# version1_3.net
KiCad netlist of a schematic drawn in EAGLE
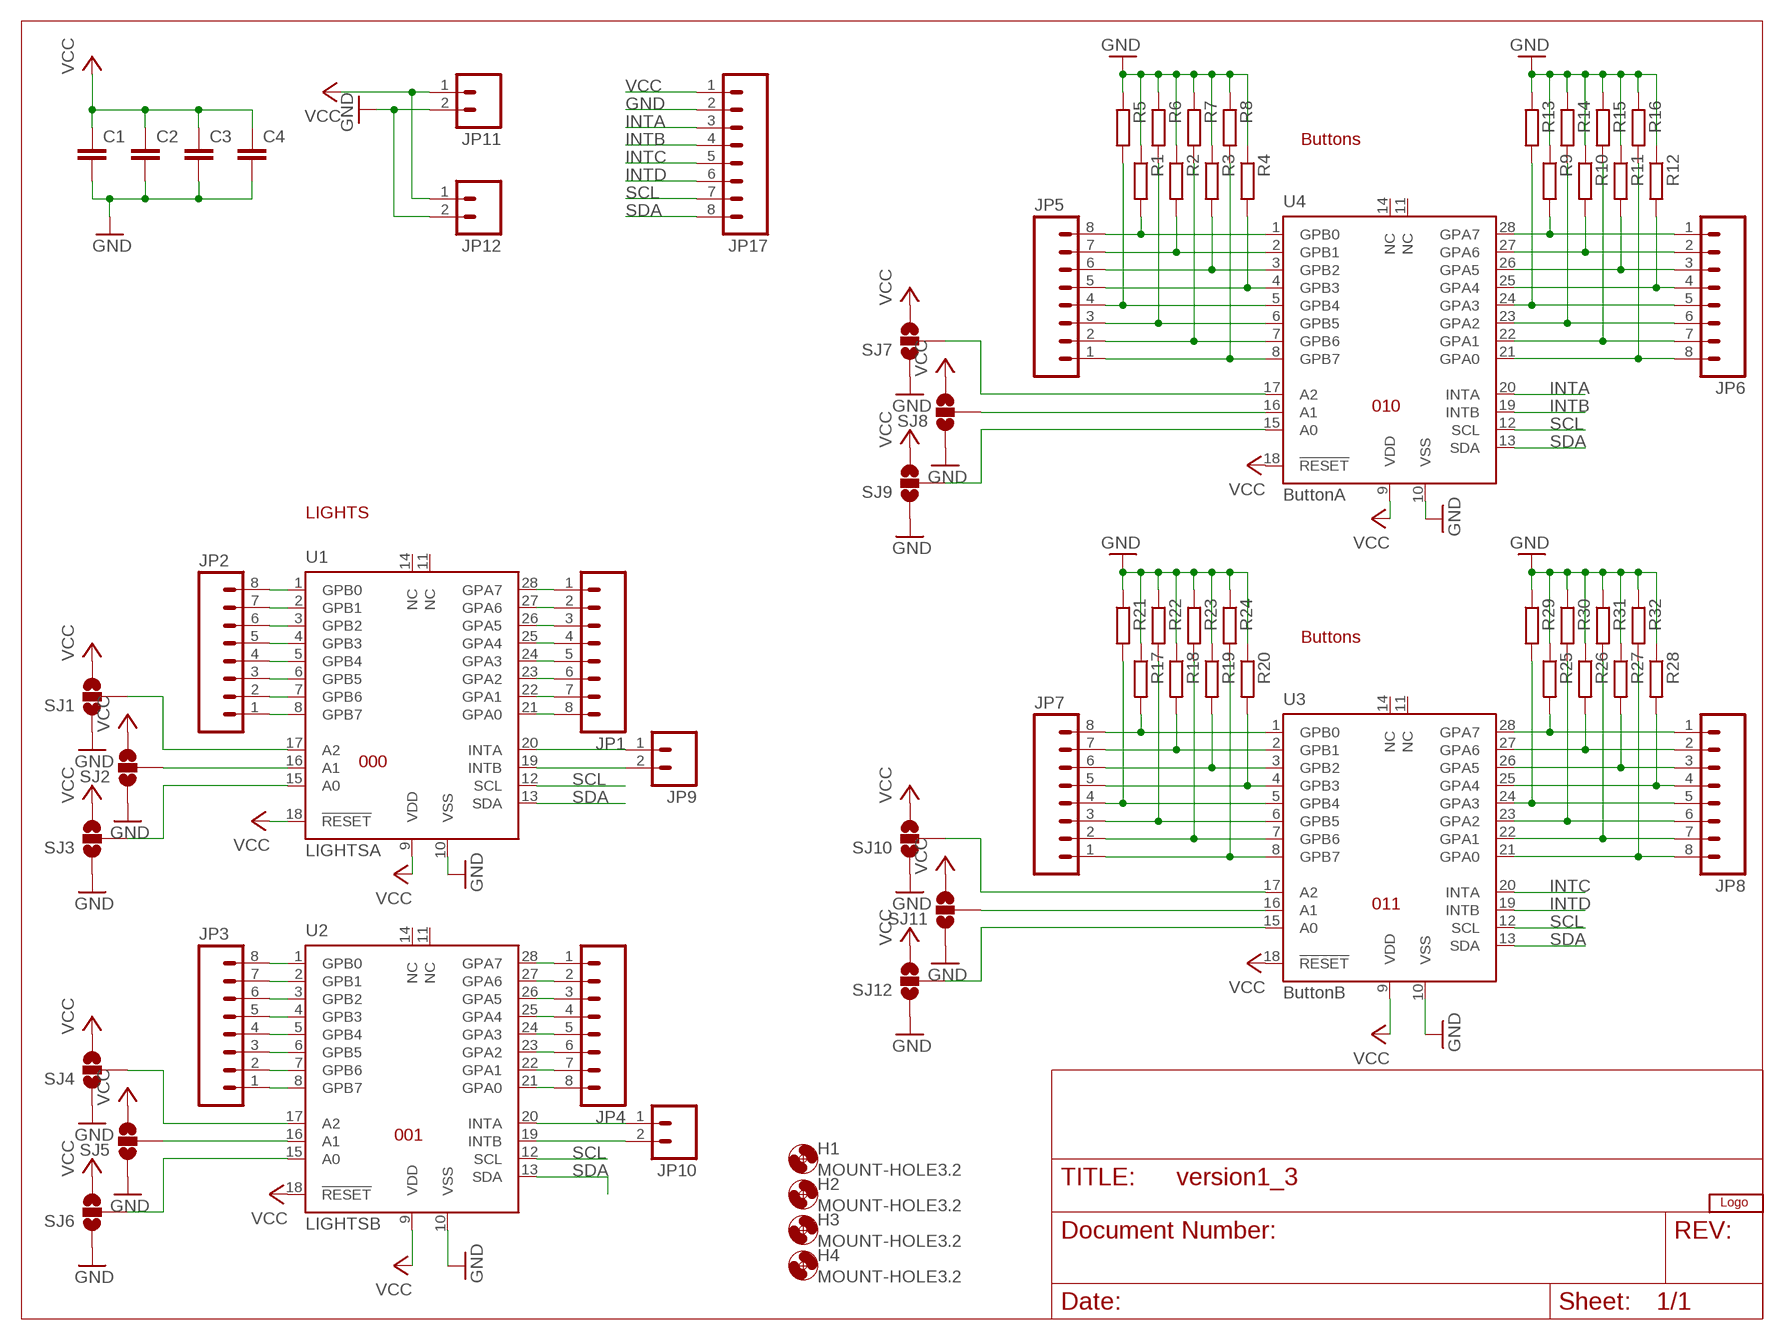
[diagram p0: schematic, sheet 1]

(export (version "E")
  (design (tool "Eeschema 10.0.6"))
  (components
    (comp (ref "C1")
      (value "C-EUC0805")
      (footprint "eagle-import:C0805")
      (libsource (lib "eagle-import") (part "C-EUC0805"))
    )
    (comp (ref "C2")
      (value "C-EUC0805")
      (footprint "eagle-import:C0805")
      (libsource (lib "eagle-import") (part "C-EUC0805"))
    )
    (comp (ref "C3")
      (value "C-EUC0805")
      (footprint "eagle-import:C0805")
      (libsource (lib "eagle-import") (part "C-EUC0805"))
    )
    (comp (ref "C4")
      (value "C-EUC0805")
      (footprint "eagle-import:C0805")
      (libsource (lib "eagle-import") (part "C-EUC0805"))
    )
    (comp (ref "H1")
      (value "MOUNT-HOLE3.2")
      (footprint "eagle-import:3,2")
      (libsource (lib "eagle-import") (part "MOUNT-HOLE3.2"))
    )
    (comp (ref "H2")
      (value "MOUNT-HOLE3.2")
      (footprint "eagle-import:3,2")
      (libsource (lib "eagle-import") (part "MOUNT-HOLE3.2"))
    )
    (comp (ref "H3")
      (value "MOUNT-HOLE3.2")
      (footprint "eagle-import:3,2")
      (libsource (lib "eagle-import") (part "MOUNT-HOLE3.2"))
    )
    (comp (ref "H4")
      (value "MOUNT-HOLE3.2")
      (footprint "eagle-import:3,2")
      (libsource (lib "eagle-import") (part "MOUNT-HOLE3.2"))
    )
    (comp (ref "JP1")
      (value "M08LOCK")
      (footprint "eagle-import:1X08_LOCK")
      (libsource (lib "eagle-import") (part "M08LOCK"))
    )
    (comp (ref "JP2")
      (value "M08LOCK")
      (footprint "eagle-import:1X08_LOCK")
      (libsource (lib "eagle-import") (part "M08LOCK"))
    )
    (comp (ref "JP3")
      (value "M08LOCK")
      (footprint "eagle-import:1X08_LOCK")
      (libsource (lib "eagle-import") (part "M08LOCK"))
    )
    (comp (ref "JP4")
      (value "M08LOCK")
      (footprint "eagle-import:1X08_LOCK")
      (libsource (lib "eagle-import") (part "M08LOCK"))
    )
    (comp (ref "JP5")
      (value "M08LOCK")
      (footprint "eagle-import:1X08_LOCK")
      (libsource (lib "eagle-import") (part "M08LOCK"))
    )
    (comp (ref "JP6")
      (value "M08LOCK")
      (footprint "eagle-import:1X08_LOCK")
      (libsource (lib "eagle-import") (part "M08LOCK"))
    )
    (comp (ref "JP7")
      (value "M08LOCK")
      (footprint "eagle-import:1X08_LOCK")
      (libsource (lib "eagle-import") (part "M08LOCK"))
    )
    (comp (ref "JP8")
      (value "M08LOCK")
      (footprint "eagle-import:1X08_LOCK")
      (libsource (lib "eagle-import") (part "M08LOCK"))
    )
    (comp (ref "JP9")
      (value "M021X02_NO_SILK")
      (footprint "eagle-import:1X02_NO_SILK")
      (libsource (lib "eagle-import") (part "M021X02_NO_SILK"))
    )
    (comp (ref "JP10")
      (value "M021X02_NO_SILK")
      (footprint "eagle-import:1X02_NO_SILK")
      (libsource (lib "eagle-import") (part "M021X02_NO_SILK"))
    )
    (comp (ref "JP11")
      (value "M021X02_NO_SILK")
      (footprint "eagle-import:1X02_NO_SILK")
      (libsource (lib "eagle-import") (part "M021X02_NO_SILK"))
    )
    (comp (ref "JP12")
      (value "M021X02_NO_SILK")
      (footprint "eagle-import:1X02_NO_SILK")
      (libsource (lib "eagle-import") (part "M021X02_NO_SILK"))
    )
    (comp (ref "JP17")
      (value "M08LOCK")
      (footprint "eagle-import:1X08_LOCK")
      (libsource (lib "eagle-import") (part "M08LOCK"))
    )
    (comp (ref "R1")
      (value "R-EU_R0805")
      (footprint "eagle-import:R0805")
      (libsource (lib "eagle-import") (part "R-EU_R0805"))
    )
    (comp (ref "R2")
      (value "R-EU_R0805")
      (footprint "eagle-import:R0805")
      (libsource (lib "eagle-import") (part "R-EU_R0805"))
    )
    (comp (ref "R3")
      (value "R-EU_R0805")
      (footprint "eagle-import:R0805")
      (libsource (lib "eagle-import") (part "R-EU_R0805"))
    )
    (comp (ref "R4")
      (value "R-EU_R0805")
      (footprint "eagle-import:R0805")
      (libsource (lib "eagle-import") (part "R-EU_R0805"))
    )
    (comp (ref "R5")
      (value "R-EU_R0805")
      (footprint "eagle-import:R0805")
      (libsource (lib "eagle-import") (part "R-EU_R0805"))
    )
    (comp (ref "R6")
      (value "R-EU_R0805")
      (footprint "eagle-import:R0805")
      (libsource (lib "eagle-import") (part "R-EU_R0805"))
    )
    (comp (ref "R7")
      (value "R-EU_R0805")
      (footprint "eagle-import:R0805")
      (libsource (lib "eagle-import") (part "R-EU_R0805"))
    )
    (comp (ref "R8")
      (value "R-EU_R0805")
      (footprint "eagle-import:R0805")
      (libsource (lib "eagle-import") (part "R-EU_R0805"))
    )
    (comp (ref "R9")
      (value "R-EU_R0805")
      (footprint "eagle-import:R0805")
      (libsource (lib "eagle-import") (part "R-EU_R0805"))
    )
    (comp (ref "R10")
      (value "R-EU_R0805")
      (footprint "eagle-import:R0805")
      (libsource (lib "eagle-import") (part "R-EU_R0805"))
    )
    (comp (ref "R11")
      (value "R-EU_R0805")
      (footprint "eagle-import:R0805")
      (libsource (lib "eagle-import") (part "R-EU_R0805"))
    )
    (comp (ref "R12")
      (value "R-EU_R0805")
      (footprint "eagle-import:R0805")
      (libsource (lib "eagle-import") (part "R-EU_R0805"))
    )
    (comp (ref "R13")
      (value "R-EU_R0805")
      (footprint "eagle-import:R0805")
      (libsource (lib "eagle-import") (part "R-EU_R0805"))
    )
    (comp (ref "R14")
      (value "R-EU_R0805")
      (footprint "eagle-import:R0805")
      (libsource (lib "eagle-import") (part "R-EU_R0805"))
    )
    (comp (ref "R15")
      (value "R-EU_R0805")
      (footprint "eagle-import:R0805")
      (libsource (lib "eagle-import") (part "R-EU_R0805"))
    )
    (comp (ref "R16")
      (value "R-EU_R0805")
      (footprint "eagle-import:R0805")
      (libsource (lib "eagle-import") (part "R-EU_R0805"))
    )
    (comp (ref "R17")
      (value "R-EU_R0805")
      (footprint "eagle-import:R0805")
      (libsource (lib "eagle-import") (part "R-EU_R0805"))
    )
    (comp (ref "R18")
      (value "R-EU_R0805")
      (footprint "eagle-import:R0805")
      (libsource (lib "eagle-import") (part "R-EU_R0805"))
    )
    (comp (ref "R19")
      (value "R-EU_R0805")
      (footprint "eagle-import:R0805")
      (libsource (lib "eagle-import") (part "R-EU_R0805"))
    )
    (comp (ref "R20")
      (value "R-EU_R0805")
      (footprint "eagle-import:R0805")
      (libsource (lib "eagle-import") (part "R-EU_R0805"))
    )
    (comp (ref "R21")
      (value "R-EU_R0805")
      (footprint "eagle-import:R0805")
      (libsource (lib "eagle-import") (part "R-EU_R0805"))
    )
    (comp (ref "R22")
      (value "R-EU_R0805")
      (footprint "eagle-import:R0805")
      (libsource (lib "eagle-import") (part "R-EU_R0805"))
    )
    (comp (ref "R23")
      (value "R-EU_R0805")
      (footprint "eagle-import:R0805")
      (libsource (lib "eagle-import") (part "R-EU_R0805"))
    )
    (comp (ref "R24")
      (value "R-EU_R0805")
      (footprint "eagle-import:R0805")
      (libsource (lib "eagle-import") (part "R-EU_R0805"))
    )
    (comp (ref "R25")
      (value "R-EU_R0805")
      (footprint "eagle-import:R0805")
      (libsource (lib "eagle-import") (part "R-EU_R0805"))
    )
    (comp (ref "R26")
      (value "R-EU_R0805")
      (footprint "eagle-import:R0805")
      (libsource (lib "eagle-import") (part "R-EU_R0805"))
    )
    (comp (ref "R27")
      (value "R-EU_R0805")
      (footprint "eagle-import:R0805")
      (libsource (lib "eagle-import") (part "R-EU_R0805"))
    )
    (comp (ref "R28")
      (value "R-EU_R0805")
      (footprint "eagle-import:R0805")
      (libsource (lib "eagle-import") (part "R-EU_R0805"))
    )
    (comp (ref "R29")
      (value "R-EU_R0805")
      (footprint "eagle-import:R0805")
      (libsource (lib "eagle-import") (part "R-EU_R0805"))
    )
    (comp (ref "R30")
      (value "R-EU_R0805")
      (footprint "eagle-import:R0805")
      (libsource (lib "eagle-import") (part "R-EU_R0805"))
    )
    (comp (ref "R31")
      (value "R-EU_R0805")
      (footprint "eagle-import:R0805")
      (libsource (lib "eagle-import") (part "R-EU_R0805"))
    )
    (comp (ref "R32")
      (value "R-EU_R0805")
      (footprint "eagle-import:R0805")
      (libsource (lib "eagle-import") (part "R-EU_R0805"))
    )
    (comp (ref "SJ1")
      (value "SOLDERJUMPER_2WAY-OLDS")
      (footprint "eagle-import:SJ_3")
      (libsource (lib "eagle-import") (part "SOLDERJUMPER_2WAY-OLDS"))
    )
    (comp (ref "SJ2")
      (value "SOLDERJUMPER_2WAY-OLDS")
      (footprint "eagle-import:SJ_3")
      (libsource (lib "eagle-import") (part "SOLDERJUMPER_2WAY-OLDS"))
    )
    (comp (ref "SJ3")
      (value "SOLDERJUMPER_2WAY-OLDS")
      (footprint "eagle-import:SJ_3")
      (libsource (lib "eagle-import") (part "SOLDERJUMPER_2WAY-OLDS"))
    )
    (comp (ref "SJ4")
      (value "SOLDERJUMPER_2WAY-OLDS")
      (footprint "eagle-import:SJ_3")
      (libsource (lib "eagle-import") (part "SOLDERJUMPER_2WAY-OLDS"))
    )
    (comp (ref "SJ5")
      (value "SOLDERJUMPER_2WAY-OLDS")
      (footprint "eagle-import:SJ_3")
      (libsource (lib "eagle-import") (part "SOLDERJUMPER_2WAY-OLDS"))
    )
    (comp (ref "SJ6")
      (value "SOLDERJUMPER_2WAY-OLDS")
      (footprint "eagle-import:SJ_3")
      (libsource (lib "eagle-import") (part "SOLDERJUMPER_2WAY-OLDS"))
    )
    (comp (ref "SJ7")
      (value "SOLDERJUMPER_2WAY-OLDS")
      (footprint "eagle-import:SJ_3")
      (libsource (lib "eagle-import") (part "SOLDERJUMPER_2WAY-OLDS"))
    )
    (comp (ref "SJ8")
      (value "SOLDERJUMPER_2WAY-OLDS")
      (footprint "eagle-import:SJ_3")
      (libsource (lib "eagle-import") (part "SOLDERJUMPER_2WAY-OLDS"))
    )
    (comp (ref "SJ9")
      (value "SOLDERJUMPER_2WAY-OLDS")
      (footprint "eagle-import:SJ_3")
      (libsource (lib "eagle-import") (part "SOLDERJUMPER_2WAY-OLDS"))
    )
    (comp (ref "SJ10")
      (value "SOLDERJUMPER_2WAY-OLDS")
      (footprint "eagle-import:SJ_3")
      (libsource (lib "eagle-import") (part "SOLDERJUMPER_2WAY-OLDS"))
    )
    (comp (ref "SJ11")
      (value "SOLDERJUMPER_2WAY-OLDS")
      (footprint "eagle-import:SJ_3")
      (libsource (lib "eagle-import") (part "SOLDERJUMPER_2WAY-OLDS"))
    )
    (comp (ref "SJ12")
      (value "SOLDERJUMPER_2WAY-OLDS")
      (footprint "eagle-import:SJ_3")
      (libsource (lib "eagle-import") (part "SOLDERJUMPER_2WAY-OLDS"))
    )
    (comp (ref "U$1")
      (value "BUNNYLOGOCALVIN2")
      (footprint "eagle-import:CALVIN2")
      (libsource (lib "eagle-import") (part "BUNNYLOGOCALVIN2"))
    )
    (comp (ref "U1")
      (value "LIGHTSA")
      (footprint "eagle-import:MCP23017A")
      (libsource (lib "eagle-import") (part "MCP23017A"))
    )
    (comp (ref "U2")
      (value "LIGHTSB")
      (footprint "eagle-import:MCP23017A")
      (libsource (lib "eagle-import") (part "MCP23017A"))
    )
    (comp (ref "U3")
      (value "ButtonB")
      (footprint "eagle-import:MCP23017A")
      (libsource (lib "eagle-import") (part "MCP23017A"))
    )
    (comp (ref "U4")
      (value "ButtonA")
      (footprint "eagle-import:MCP23017A")
      (libsource (lib "eagle-import") (part "MCP23017A"))
    )
  )
  (nets
    (net (code "1") (name "/INTA") (class "Default")
      (node (ref "JP17") (pin "3") (pinfunction "3_3") (pintype "passive"))
      (node (ref "U4") (pin "20") (pinfunction "INTA_20") (pintype "bidirectional"))
    )
    (net (code "2") (name "/INTB") (class "Default")
      (node (ref "JP17") (pin "4") (pinfunction "4_4") (pintype "passive"))
      (node (ref "U4") (pin "19") (pinfunction "INTB_19") (pintype "bidirectional"))
    )
    (net (code "3") (name "/INTC") (class "Default")
      (node (ref "JP17") (pin "5") (pinfunction "5_5") (pintype "passive"))
      (node (ref "U3") (pin "20") (pinfunction "INTA_20") (pintype "bidirectional"))
    )
    (net (code "4") (name "/INTD") (class "Default")
      (node (ref "JP17") (pin "6") (pinfunction "6_6") (pintype "passive"))
      (node (ref "U3") (pin "19") (pinfunction "INTB_19") (pintype "bidirectional"))
    )
    (net (code "5") (name "/SCL") (class "Default")
      (node (ref "JP17") (pin "7") (pinfunction "7_7") (pintype "passive"))
      (node (ref "U1") (pin "12") (pinfunction "SCL_12") (pintype "bidirectional"))
      (node (ref "U2") (pin "12") (pinfunction "SCL_12") (pintype "bidirectional"))
      (node (ref "U3") (pin "12") (pinfunction "SCL_12") (pintype "bidirectional"))
      (node (ref "U4") (pin "12") (pinfunction "SCL_12") (pintype "bidirectional"))
    )
    (net (code "6") (name "/SDA") (class "Default")
      (node (ref "JP17") (pin "8") (pinfunction "8_8") (pintype "passive"))
      (node (ref "U1") (pin "13") (pinfunction "SDA_13") (pintype "bidirectional"))
      (node (ref "U2") (pin "13") (pinfunction "SDA_13") (pintype "bidirectional"))
      (node (ref "U3") (pin "13") (pinfunction "SDA_13") (pintype "bidirectional"))
      (node (ref "U4") (pin "13") (pinfunction "SDA_13") (pintype "bidirectional"))
    )
    (net (code "7") (name "GND") (class "Default")
      (node (ref "C1") (pin "2") (pinfunction "2_2") (pintype "passive"))
      (node (ref "C2") (pin "2") (pinfunction "2_2") (pintype "passive"))
      (node (ref "C3") (pin "2") (pinfunction "2_2") (pintype "passive"))
      (node (ref "C4") (pin "2") (pinfunction "2_2") (pintype "passive"))
      (node (ref "JP11") (pin "2") (pinfunction "2_2") (pintype "passive"))
      (node (ref "JP12") (pin "2") (pinfunction "2_2") (pintype "passive"))
      (node (ref "JP17") (pin "2") (pinfunction "2_2") (pintype "passive"))
      (node (ref "R1") (pin "1") (pinfunction "1_1") (pintype "passive"))
      (node (ref "R10") (pin "1") (pinfunction "1_1") (pintype "passive"))
      (node (ref "R11") (pin "1") (pinfunction "1_1") (pintype "passive"))
      (node (ref "R12") (pin "1") (pinfunction "1_1") (pintype "passive"))
      (node (ref "R13") (pin "1") (pinfunction "1_1") (pintype "passive"))
      (node (ref "R14") (pin "1") (pinfunction "1_1") (pintype "passive"))
      (node (ref "R15") (pin "1") (pinfunction "1_1") (pintype "passive"))
      (node (ref "R16") (pin "1") (pinfunction "1_1") (pintype "passive"))
      (node (ref "R17") (pin "1") (pinfunction "1_1") (pintype "passive"))
      (node (ref "R18") (pin "1") (pinfunction "1_1") (pintype "passive"))
      (node (ref "R19") (pin "1") (pinfunction "1_1") (pintype "passive"))
      (node (ref "R2") (pin "1") (pinfunction "1_1") (pintype "passive"))
      (node (ref "R20") (pin "1") (pinfunction "1_1") (pintype "passive"))
      (node (ref "R21") (pin "1") (pinfunction "1_1") (pintype "passive"))
      (node (ref "R22") (pin "1") (pinfunction "1_1") (pintype "passive"))
      (node (ref "R23") (pin "1") (pinfunction "1_1") (pintype "passive"))
      (node (ref "R24") (pin "1") (pinfunction "1_1") (pintype "passive"))
      (node (ref "R25") (pin "1") (pinfunction "1_1") (pintype "passive"))
      (node (ref "R26") (pin "1") (pinfunction "1_1") (pintype "passive"))
      (node (ref "R27") (pin "1") (pinfunction "1_1") (pintype "passive"))
      (node (ref "R28") (pin "1") (pinfunction "1_1") (pintype "passive"))
      (node (ref "R29") (pin "1") (pinfunction "1_1") (pintype "passive"))
      (node (ref "R3") (pin "1") (pinfunction "1_1") (pintype "passive"))
      (node (ref "R30") (pin "1") (pinfunction "1_1") (pintype "passive"))
      (node (ref "R31") (pin "1") (pinfunction "1_1") (pintype "passive"))
      (node (ref "R32") (pin "1") (pinfunction "1_1") (pintype "passive"))
      (node (ref "R4") (pin "1") (pinfunction "1_1") (pintype "passive"))
      (node (ref "R5") (pin "1") (pinfunction "1_1") (pintype "passive"))
      (node (ref "R6") (pin "1") (pinfunction "1_1") (pintype "passive"))
      (node (ref "R7") (pin "1") (pinfunction "1_1") (pintype "passive"))
      (node (ref "R8") (pin "1") (pinfunction "1_1") (pintype "passive"))
      (node (ref "R9") (pin "1") (pinfunction "1_1") (pintype "passive"))
      (node (ref "SJ1") (pin "1") (pinfunction "1_1") (pintype "passive"))
      (node (ref "SJ10") (pin "1") (pinfunction "1_1") (pintype "passive"))
      (node (ref "SJ11") (pin "1") (pinfunction "1_1") (pintype "passive"))
      (node (ref "SJ12") (pin "1") (pinfunction "1_1") (pintype "passive"))
      (node (ref "SJ2") (pin "1") (pinfunction "1_1") (pintype "passive"))
      (node (ref "SJ3") (pin "1") (pinfunction "1_1") (pintype "passive"))
      (node (ref "SJ4") (pin "1") (pinfunction "1_1") (pintype "passive"))
      (node (ref "SJ5") (pin "1") (pinfunction "1_1") (pintype "passive"))
      (node (ref "SJ6") (pin "1") (pinfunction "1_1") (pintype "passive"))
      (node (ref "SJ7") (pin "1") (pinfunction "1_1") (pintype "passive"))
      (node (ref "SJ8") (pin "1") (pinfunction "1_1") (pintype "passive"))
      (node (ref "SJ9") (pin "1") (pinfunction "1_1") (pintype "passive"))
      (node (ref "U1") (pin "10") (pinfunction "VSS_10") (pintype "power_in"))
      (node (ref "U2") (pin "10") (pinfunction "VSS_10") (pintype "power_in"))
      (node (ref "U3") (pin "10") (pinfunction "VSS_10") (pintype "power_in"))
      (node (ref "U4") (pin "10") (pinfunction "VSS_10") (pintype "power_in"))
    )
    (net (code "8") (name "Net-(U1-A0)") (class "Default")
      (node (ref "SJ3") (pin "2") (pinfunction "2_2") (pintype "passive"))
      (node (ref "U1") (pin "15") (pinfunction "A0_15") (pintype "bidirectional"))
    )
    (net (code "9") (name "Net-(U1-A1)") (class "Default")
      (node (ref "SJ2") (pin "2") (pinfunction "2_2") (pintype "passive"))
      (node (ref "U1") (pin "16") (pinfunction "A1_16") (pintype "bidirectional"))
    )
    (net (code "10") (name "Net-(U1-A2)") (class "Default")
      (node (ref "SJ1") (pin "2") (pinfunction "2_2") (pintype "passive"))
      (node (ref "U1") (pin "17") (pinfunction "A2_17") (pintype "bidirectional"))
    )
    (net (code "11") (name "Net-(U1-GPA0)") (class "Default")
      (node (ref "JP1") (pin "8") (pinfunction "8_8") (pintype "passive"))
      (node (ref "U1") (pin "21") (pinfunction "GPA0_21") (pintype "bidirectional"))
    )
    (net (code "12") (name "Net-(U1-GPA1)") (class "Default")
      (node (ref "JP1") (pin "7") (pinfunction "7_7") (pintype "passive"))
      (node (ref "U1") (pin "22") (pinfunction "GPA1_22") (pintype "bidirectional"))
    )
    (net (code "13") (name "Net-(U1-GPA2)") (class "Default")
      (node (ref "JP1") (pin "6") (pinfunction "6_6") (pintype "passive"))
      (node (ref "U1") (pin "23") (pinfunction "GPA2_23") (pintype "bidirectional"))
    )
    (net (code "14") (name "Net-(U1-GPA3)") (class "Default")
      (node (ref "JP1") (pin "5") (pinfunction "5_5") (pintype "passive"))
      (node (ref "U1") (pin "24") (pinfunction "GPA3_24") (pintype "bidirectional"))
    )
    (net (code "15") (name "Net-(U1-GPA4)") (class "Default")
      (node (ref "JP1") (pin "4") (pinfunction "4_4") (pintype "passive"))
      (node (ref "U1") (pin "25") (pinfunction "GPA4_25") (pintype "bidirectional"))
    )
    (net (code "16") (name "Net-(U1-GPA5)") (class "Default")
      (node (ref "JP1") (pin "3") (pinfunction "3_3") (pintype "passive"))
      (node (ref "U1") (pin "26") (pinfunction "GPA5_26") (pintype "bidirectional"))
    )
    (net (code "17") (name "Net-(U1-GPA6)") (class "Default")
      (node (ref "JP1") (pin "2") (pinfunction "2_2") (pintype "passive"))
      (node (ref "U1") (pin "27") (pinfunction "GPA6_27") (pintype "bidirectional"))
    )
    (net (code "18") (name "Net-(U1-GPA7)") (class "Default")
      (node (ref "JP1") (pin "1") (pinfunction "1_1") (pintype "passive"))
      (node (ref "U1") (pin "28") (pinfunction "GPA7_28") (pintype "bidirectional"))
    )
    (net (code "19") (name "Net-(U1-GPB0)") (class "Default")
      (node (ref "JP2") (pin "8") (pinfunction "8_8") (pintype "passive"))
      (node (ref "U1") (pin "1") (pinfunction "GPB0_1") (pintype "bidirectional"))
    )
    (net (code "20") (name "Net-(U1-GPB1)") (class "Default")
      (node (ref "JP2") (pin "7") (pinfunction "7_7") (pintype "passive"))
      (node (ref "U1") (pin "2") (pinfunction "GPB1_2") (pintype "bidirectional"))
    )
    (net (code "21") (name "Net-(U1-GPB2)") (class "Default")
      (node (ref "JP2") (pin "6") (pinfunction "6_6") (pintype "passive"))
      (node (ref "U1") (pin "3") (pinfunction "GPB2_3") (pintype "bidirectional"))
    )
    (net (code "22") (name "Net-(U1-GPB3)") (class "Default")
      (node (ref "JP2") (pin "5") (pinfunction "5_5") (pintype "passive"))
      (node (ref "U1") (pin "4") (pinfunction "GPB3_4") (pintype "bidirectional"))
    )
    (net (code "23") (name "Net-(U1-GPB4)") (class "Default")
      (node (ref "JP2") (pin "4") (pinfunction "4_4") (pintype "passive"))
      (node (ref "U1") (pin "5") (pinfunction "GPB4_5") (pintype "bidirectional"))
    )
    (net (code "24") (name "Net-(U1-GPB5)") (class "Default")
      (node (ref "JP2") (pin "3") (pinfunction "3_3") (pintype "passive"))
      (node (ref "U1") (pin "6") (pinfunction "GPB5_6") (pintype "bidirectional"))
    )
    (net (code "25") (name "Net-(U1-GPB6)") (class "Default")
      (node (ref "JP2") (pin "2") (pinfunction "2_2") (pintype "passive"))
      (node (ref "U1") (pin "7") (pinfunction "GPB6_7") (pintype "bidirectional"))
    )
    (net (code "26") (name "Net-(U1-GPB7)") (class "Default")
      (node (ref "JP2") (pin "1") (pinfunction "1_1") (pintype "passive"))
      (node (ref "U1") (pin "8") (pinfunction "GPB7_8") (pintype "bidirectional"))
    )
    (net (code "27") (name "Net-(U1-INTA)") (class "Default")
      (node (ref "JP9") (pin "1") (pinfunction "1_1") (pintype "passive"))
      (node (ref "U1") (pin "20") (pinfunction "INTA_20") (pintype "bidirectional"))
    )
    (net (code "28") (name "Net-(U1-INTB)") (class "Default")
      (node (ref "JP9") (pin "2") (pinfunction "2_2") (pintype "passive"))
      (node (ref "U1") (pin "19") (pinfunction "INTB_19") (pintype "bidirectional"))
    )
    (net (code "29") (name "Net-(U2-A0)") (class "Default")
      (node (ref "SJ6") (pin "2") (pinfunction "2_2") (pintype "passive"))
      (node (ref "U2") (pin "15") (pinfunction "A0_15") (pintype "bidirectional"))
    )
    (net (code "30") (name "Net-(U2-A1)") (class "Default")
      (node (ref "SJ5") (pin "2") (pinfunction "2_2") (pintype "passive"))
      (node (ref "U2") (pin "16") (pinfunction "A1_16") (pintype "bidirectional"))
    )
    (net (code "31") (name "Net-(U2-A2)") (class "Default")
      (node (ref "SJ4") (pin "2") (pinfunction "2_2") (pintype "passive"))
      (node (ref "U2") (pin "17") (pinfunction "A2_17") (pintype "bidirectional"))
    )
    (net (code "32") (name "Net-(U2-GPA0)") (class "Default")
      (node (ref "JP4") (pin "8") (pinfunction "8_8") (pintype "passive"))
      (node (ref "U2") (pin "21") (pinfunction "GPA0_21") (pintype "bidirectional"))
    )
    (net (code "33") (name "Net-(U2-GPA1)") (class "Default")
      (node (ref "JP4") (pin "7") (pinfunction "7_7") (pintype "passive"))
      (node (ref "U2") (pin "22") (pinfunction "GPA1_22") (pintype "bidirectional"))
    )
    (net (code "34") (name "Net-(U2-GPA2)") (class "Default")
      (node (ref "JP4") (pin "6") (pinfunction "6_6") (pintype "passive"))
      (node (ref "U2") (pin "23") (pinfunction "GPA2_23") (pintype "bidirectional"))
    )
    (net (code "35") (name "Net-(U2-GPA3)") (class "Default")
      (node (ref "JP4") (pin "5") (pinfunction "5_5") (pintype "passive"))
      (node (ref "U2") (pin "24") (pinfunction "GPA3_24") (pintype "bidirectional"))
    )
    (net (code "36") (name "Net-(U2-GPA4)") (class "Default")
      (node (ref "JP4") (pin "4") (pinfunction "4_4") (pintype "passive"))
      (node (ref "U2") (pin "25") (pinfunction "GPA4_25") (pintype "bidirectional"))
    )
    (net (code "37") (name "Net-(U2-GPA5)") (class "Default")
      (node (ref "JP4") (pin "3") (pinfunction "3_3") (pintype "passive"))
      (node (ref "U2") (pin "26") (pinfunction "GPA5_26") (pintype "bidirectional"))
    )
    (net (code "38") (name "Net-(U2-GPA6)") (class "Default")
      (node (ref "JP4") (pin "2") (pinfunction "2_2") (pintype "passive"))
      (node (ref "U2") (pin "27") (pinfunction "GPA6_27") (pintype "bidirectional"))
    )
    (net (code "39") (name "Net-(U2-GPA7)") (class "Default")
      (node (ref "JP4") (pin "1") (pinfunction "1_1") (pintype "passive"))
      (node (ref "U2") (pin "28") (pinfunction "GPA7_28") (pintype "bidirectional"))
    )
    (net (code "40") (name "Net-(U2-GPB0)") (class "Default")
      (node (ref "JP3") (pin "8") (pinfunction "8_8") (pintype "passive"))
      (node (ref "U2") (pin "1") (pinfunction "GPB0_1") (pintype "bidirectional"))
    )
    (net (code "41") (name "Net-(U2-GPB1)") (class "Default")
      (node (ref "JP3") (pin "7") (pinfunction "7_7") (pintype "passive"))
      (node (ref "U2") (pin "2") (pinfunction "GPB1_2") (pintype "bidirectional"))
    )
    (net (code "42") (name "Net-(U2-GPB2)") (class "Default")
      (node (ref "JP3") (pin "6") (pinfunction "6_6") (pintype "passive"))
      (node (ref "U2") (pin "3") (pinfunction "GPB2_3") (pintype "bidirectional"))
    )
    (net (code "43") (name "Net-(U2-GPB3)") (class "Default")
      (node (ref "JP3") (pin "5") (pinfunction "5_5") (pintype "passive"))
      (node (ref "U2") (pin "4") (pinfunction "GPB3_4") (pintype "bidirectional"))
    )
    (net (code "44") (name "Net-(U2-GPB4)") (class "Default")
      (node (ref "JP3") (pin "4") (pinfunction "4_4") (pintype "passive"))
      (node (ref "U2") (pin "5") (pinfunction "GPB4_5") (pintype "bidirectional"))
    )
    (net (code "45") (name "Net-(U2-GPB5)") (class "Default")
      (node (ref "JP3") (pin "3") (pinfunction "3_3") (pintype "passive"))
      (node (ref "U2") (pin "6") (pinfunction "GPB5_6") (pintype "bidirectional"))
    )
    (net (code "46") (name "Net-(U2-GPB6)") (class "Default")
      (node (ref "JP3") (pin "2") (pinfunction "2_2") (pintype "passive"))
      (node (ref "U2") (pin "7") (pinfunction "GPB6_7") (pintype "bidirectional"))
    )
    (net (code "47") (name "Net-(U2-GPB7)") (class "Default")
      (node (ref "JP3") (pin "1") (pinfunction "1_1") (pintype "passive"))
      (node (ref "U2") (pin "8") (pinfunction "GPB7_8") (pintype "bidirectional"))
    )
    (net (code "48") (name "Net-(U2-INTA)") (class "Default")
      (node (ref "JP10") (pin "1") (pinfunction "1_1") (pintype "passive"))
      (node (ref "U2") (pin "20") (pinfunction "INTA_20") (pintype "bidirectional"))
    )
    (net (code "49") (name "Net-(U2-INTB)") (class "Default")
      (node (ref "JP10") (pin "2") (pinfunction "2_2") (pintype "passive"))
      (node (ref "U2") (pin "19") (pinfunction "INTB_19") (pintype "bidirectional"))
    )
    (net (code "50") (name "Net-(U3-A0)") (class "Default")
      (node (ref "SJ12") (pin "2") (pinfunction "2_2") (pintype "passive"))
      (node (ref "U3") (pin "15") (pinfunction "A0_15") (pintype "bidirectional"))
    )
    (net (code "51") (name "Net-(U3-A1)") (class "Default")
      (node (ref "SJ11") (pin "2") (pinfunction "2_2") (pintype "passive"))
      (node (ref "U3") (pin "16") (pinfunction "A1_16") (pintype "bidirectional"))
    )
    (net (code "52") (name "Net-(U3-A2)") (class "Default")
      (node (ref "SJ10") (pin "2") (pinfunction "2_2") (pintype "passive"))
      (node (ref "U3") (pin "17") (pinfunction "A2_17") (pintype "bidirectional"))
    )
    (net (code "53") (name "Net-(U3-GPA0)") (class "Default")
      (node (ref "JP8") (pin "8") (pinfunction "8_8") (pintype "passive"))
      (node (ref "R32") (pin "2") (pinfunction "2_2") (pintype "passive"))
      (node (ref "U3") (pin "21") (pinfunction "GPA0_21") (pintype "bidirectional"))
    )
    (net (code "54") (name "Net-(U3-GPA1)") (class "Default")
      (node (ref "JP8") (pin "7") (pinfunction "7_7") (pintype "passive"))
      (node (ref "R31") (pin "2") (pinfunction "2_2") (pintype "passive"))
      (node (ref "U3") (pin "22") (pinfunction "GPA1_22") (pintype "bidirectional"))
    )
    (net (code "55") (name "Net-(U3-GPA2)") (class "Default")
      (node (ref "JP8") (pin "6") (pinfunction "6_6") (pintype "passive"))
      (node (ref "R30") (pin "2") (pinfunction "2_2") (pintype "passive"))
      (node (ref "U3") (pin "23") (pinfunction "GPA2_23") (pintype "bidirectional"))
    )
    (net (code "56") (name "Net-(U3-GPA3)") (class "Default")
      (node (ref "JP8") (pin "5") (pinfunction "5_5") (pintype "passive"))
      (node (ref "R29") (pin "2") (pinfunction "2_2") (pintype "passive"))
      (node (ref "U3") (pin "24") (pinfunction "GPA3_24") (pintype "bidirectional"))
    )
    (net (code "57") (name "Net-(U3-GPA4)") (class "Default")
      (node (ref "JP8") (pin "4") (pinfunction "4_4") (pintype "passive"))
      (node (ref "R28") (pin "2") (pinfunction "2_2") (pintype "passive"))
      (node (ref "U3") (pin "25") (pinfunction "GPA4_25") (pintype "bidirectional"))
    )
    (net (code "58") (name "Net-(U3-GPA5)") (class "Default")
      (node (ref "JP8") (pin "3") (pinfunction "3_3") (pintype "passive"))
      (node (ref "R27") (pin "2") (pinfunction "2_2") (pintype "passive"))
      (node (ref "U3") (pin "26") (pinfunction "GPA5_26") (pintype "bidirectional"))
    )
    (net (code "59") (name "Net-(U3-GPA6)") (class "Default")
      (node (ref "JP8") (pin "2") (pinfunction "2_2") (pintype "passive"))
      (node (ref "R26") (pin "2") (pinfunction "2_2") (pintype "passive"))
      (node (ref "U3") (pin "27") (pinfunction "GPA6_27") (pintype "bidirectional"))
    )
    (net (code "60") (name "Net-(U3-GPA7)") (class "Default")
      (node (ref "JP8") (pin "1") (pinfunction "1_1") (pintype "passive"))
      (node (ref "R25") (pin "2") (pinfunction "2_2") (pintype "passive"))
      (node (ref "U3") (pin "28") (pinfunction "GPA7_28") (pintype "bidirectional"))
    )
    (net (code "61") (name "Net-(U3-GPB0)") (class "Default")
      (node (ref "JP7") (pin "8") (pinfunction "8_8") (pintype "passive"))
      (node (ref "R17") (pin "2") (pinfunction "2_2") (pintype "passive"))
      (node (ref "U3") (pin "1") (pinfunction "GPB0_1") (pintype "bidirectional"))
    )
    (net (code "62") (name "Net-(U3-GPB1)") (class "Default")
      (node (ref "JP7") (pin "7") (pinfunction "7_7") (pintype "passive"))
      (node (ref "R18") (pin "2") (pinfunction "2_2") (pintype "passive"))
      (node (ref "U3") (pin "2") (pinfunction "GPB1_2") (pintype "bidirectional"))
    )
    (net (code "63") (name "Net-(U3-GPB2)") (class "Default")
      (node (ref "JP7") (pin "6") (pinfunction "6_6") (pintype "passive"))
      (node (ref "R19") (pin "2") (pinfunction "2_2") (pintype "passive"))
      (node (ref "U3") (pin "3") (pinfunction "GPB2_3") (pintype "bidirectional"))
    )
    (net (code "64") (name "Net-(U3-GPB3)") (class "Default")
      (node (ref "JP7") (pin "5") (pinfunction "5_5") (pintype "passive"))
      (node (ref "R20") (pin "2") (pinfunction "2_2") (pintype "passive"))
      (node (ref "U3") (pin "4") (pinfunction "GPB3_4") (pintype "bidirectional"))
    )
    (net (code "65") (name "Net-(U3-GPB4)") (class "Default")
      (node (ref "JP7") (pin "4") (pinfunction "4_4") (pintype "passive"))
      (node (ref "R21") (pin "2") (pinfunction "2_2") (pintype "passive"))
      (node (ref "U3") (pin "5") (pinfunction "GPB4_5") (pintype "bidirectional"))
    )
    (net (code "66") (name "Net-(U3-GPB5)") (class "Default")
      (node (ref "JP7") (pin "3") (pinfunction "3_3") (pintype "passive"))
      (node (ref "R22") (pin "2") (pinfunction "2_2") (pintype "passive"))
      (node (ref "U3") (pin "6") (pinfunction "GPB5_6") (pintype "bidirectional"))
    )
    (net (code "67") (name "Net-(U3-GPB6)") (class "Default")
      (node (ref "JP7") (pin "2") (pinfunction "2_2") (pintype "passive"))
      (node (ref "R23") (pin "2") (pinfunction "2_2") (pintype "passive"))
      (node (ref "U3") (pin "7") (pinfunction "GPB6_7") (pintype "bidirectional"))
    )
    (net (code "68") (name "Net-(U3-GPB7)") (class "Default")
      (node (ref "JP7") (pin "1") (pinfunction "1_1") (pintype "passive"))
      (node (ref "R24") (pin "2") (pinfunction "2_2") (pintype "passive"))
      (node (ref "U3") (pin "8") (pinfunction "GPB7_8") (pintype "bidirectional"))
    )
    (net (code "69") (name "Net-(U4-A0)") (class "Default")
      (node (ref "SJ9") (pin "2") (pinfunction "2_2") (pintype "passive"))
      (node (ref "U4") (pin "15") (pinfunction "A0_15") (pintype "bidirectional"))
    )
    (net (code "70") (name "Net-(U4-A1)") (class "Default")
      (node (ref "SJ8") (pin "2") (pinfunction "2_2") (pintype "passive"))
      (node (ref "U4") (pin "16") (pinfunction "A1_16") (pintype "bidirectional"))
    )
    (net (code "71") (name "Net-(U4-A2)") (class "Default")
      (node (ref "SJ7") (pin "2") (pinfunction "2_2") (pintype "passive"))
      (node (ref "U4") (pin "17") (pinfunction "A2_17") (pintype "bidirectional"))
    )
    (net (code "72") (name "Net-(U4-GPA0)") (class "Default")
      (node (ref "JP6") (pin "8") (pinfunction "8_8") (pintype "passive"))
      (node (ref "R16") (pin "2") (pinfunction "2_2") (pintype "passive"))
      (node (ref "U4") (pin "21") (pinfunction "GPA0_21") (pintype "bidirectional"))
    )
    (net (code "73") (name "Net-(U4-GPA1)") (class "Default")
      (node (ref "JP6") (pin "7") (pinfunction "7_7") (pintype "passive"))
      (node (ref "R15") (pin "2") (pinfunction "2_2") (pintype "passive"))
      (node (ref "U4") (pin "22") (pinfunction "GPA1_22") (pintype "bidirectional"))
    )
    (net (code "74") (name "Net-(U4-GPA2)") (class "Default")
      (node (ref "JP6") (pin "6") (pinfunction "6_6") (pintype "passive"))
      (node (ref "R14") (pin "2") (pinfunction "2_2") (pintype "passive"))
      (node (ref "U4") (pin "23") (pinfunction "GPA2_23") (pintype "bidirectional"))
    )
    (net (code "75") (name "Net-(U4-GPA3)") (class "Default")
      (node (ref "JP6") (pin "5") (pinfunction "5_5") (pintype "passive"))
      (node (ref "R13") (pin "2") (pinfunction "2_2") (pintype "passive"))
      (node (ref "U4") (pin "24") (pinfunction "GPA3_24") (pintype "bidirectional"))
    )
    (net (code "76") (name "Net-(U4-GPA4)") (class "Default")
      (node (ref "JP6") (pin "4") (pinfunction "4_4") (pintype "passive"))
      (node (ref "R12") (pin "2") (pinfunction "2_2") (pintype "passive"))
      (node (ref "U4") (pin "25") (pinfunction "GPA4_25") (pintype "bidirectional"))
    )
    (net (code "77") (name "Net-(U4-GPA5)") (class "Default")
      (node (ref "JP6") (pin "3") (pinfunction "3_3") (pintype "passive"))
      (node (ref "R11") (pin "2") (pinfunction "2_2") (pintype "passive"))
      (node (ref "U4") (pin "26") (pinfunction "GPA5_26") (pintype "bidirectional"))
    )
    (net (code "78") (name "Net-(U4-GPA6)") (class "Default")
      (node (ref "JP6") (pin "2") (pinfunction "2_2") (pintype "passive"))
      (node (ref "R10") (pin "2") (pinfunction "2_2") (pintype "passive"))
      (node (ref "U4") (pin "27") (pinfunction "GPA6_27") (pintype "bidirectional"))
    )
    (net (code "79") (name "Net-(U4-GPA7)") (class "Default")
      (node (ref "JP6") (pin "1") (pinfunction "1_1") (pintype "passive"))
      (node (ref "R9") (pin "2") (pinfunction "2_2") (pintype "passive"))
      (node (ref "U4") (pin "28") (pinfunction "GPA7_28") (pintype "bidirectional"))
    )
    (net (code "80") (name "Net-(U4-GPB0)") (class "Default")
      (node (ref "JP5") (pin "8") (pinfunction "8_8") (pintype "passive"))
      (node (ref "R1") (pin "2") (pinfunction "2_2") (pintype "passive"))
      (node (ref "U4") (pin "1") (pinfunction "GPB0_1") (pintype "bidirectional"))
    )
    (net (code "81") (name "Net-(U4-GPB1)") (class "Default")
      (node (ref "JP5") (pin "7") (pinfunction "7_7") (pintype "passive"))
      (node (ref "R2") (pin "2") (pinfunction "2_2") (pintype "passive"))
      (node (ref "U4") (pin "2") (pinfunction "GPB1_2") (pintype "bidirectional"))
    )
    (net (code "82") (name "Net-(U4-GPB2)") (class "Default")
      (node (ref "JP5") (pin "6") (pinfunction "6_6") (pintype "passive"))
      (node (ref "R3") (pin "2") (pinfunction "2_2") (pintype "passive"))
      (node (ref "U4") (pin "3") (pinfunction "GPB2_3") (pintype "bidirectional"))
    )
    (net (code "83") (name "Net-(U4-GPB3)") (class "Default")
      (node (ref "JP5") (pin "5") (pinfunction "5_5") (pintype "passive"))
      (node (ref "R4") (pin "2") (pinfunction "2_2") (pintype "passive"))
      (node (ref "U4") (pin "4") (pinfunction "GPB3_4") (pintype "bidirectional"))
    )
    (net (code "84") (name "Net-(U4-GPB4)") (class "Default")
      (node (ref "JP5") (pin "4") (pinfunction "4_4") (pintype "passive"))
      (node (ref "R5") (pin "2") (pinfunction "2_2") (pintype "passive"))
      (node (ref "U4") (pin "5") (pinfunction "GPB4_5") (pintype "bidirectional"))
    )
    (net (code "85") (name "Net-(U4-GPB5)") (class "Default")
      (node (ref "JP5") (pin "3") (pinfunction "3_3") (pintype "passive"))
      (node (ref "R6") (pin "2") (pinfunction "2_2") (pintype "passive"))
      (node (ref "U4") (pin "6") (pinfunction "GPB5_6") (pintype "bidirectional"))
    )
    (net (code "86") (name "Net-(U4-GPB6)") (class "Default")
      (node (ref "JP5") (pin "2") (pinfunction "2_2") (pintype "passive"))
      (node (ref "R7") (pin "2") (pinfunction "2_2") (pintype "passive"))
      (node (ref "U4") (pin "7") (pinfunction "GPB6_7") (pintype "bidirectional"))
    )
    (net (code "87") (name "Net-(U4-GPB7)") (class "Default")
      (node (ref "JP5") (pin "1") (pinfunction "1_1") (pintype "passive"))
      (node (ref "R8") (pin "2") (pinfunction "2_2") (pintype "passive"))
      (node (ref "U4") (pin "8") (pinfunction "GPB7_8") (pintype "bidirectional"))
    )
    (net (code "88") (name "VCC") (class "Default")
      (node (ref "C1") (pin "1") (pinfunction "1_1") (pintype "passive"))
      (node (ref "C2") (pin "1") (pinfunction "1_1") (pintype "passive"))
      (node (ref "C3") (pin "1") (pinfunction "1_1") (pintype "passive"))
      (node (ref "C4") (pin "1") (pinfunction "1_1") (pintype "passive"))
      (node (ref "JP11") (pin "1") (pinfunction "1_1") (pintype "passive"))
      (node (ref "JP12") (pin "1") (pinfunction "1_1") (pintype "passive"))
      (node (ref "JP17") (pin "1") (pinfunction "1_1") (pintype "passive"))
      (node (ref "SJ1") (pin "3") (pinfunction "3_3") (pintype "passive"))
      (node (ref "SJ10") (pin "3") (pinfunction "3_3") (pintype "passive"))
      (node (ref "SJ11") (pin "3") (pinfunction "3_3") (pintype "passive"))
      (node (ref "SJ12") (pin "3") (pinfunction "3_3") (pintype "passive"))
      (node (ref "SJ2") (pin "3") (pinfunction "3_3") (pintype "passive"))
      (node (ref "SJ3") (pin "3") (pinfunction "3_3") (pintype "passive"))
      (node (ref "SJ4") (pin "3") (pinfunction "3_3") (pintype "passive"))
      (node (ref "SJ5") (pin "3") (pinfunction "3_3") (pintype "passive"))
      (node (ref "SJ6") (pin "3") (pinfunction "3_3") (pintype "passive"))
      (node (ref "SJ7") (pin "3") (pinfunction "3_3") (pintype "passive"))
      (node (ref "SJ8") (pin "3") (pinfunction "3_3") (pintype "passive"))
      (node (ref "SJ9") (pin "3") (pinfunction "3_3") (pintype "passive"))
      (node (ref "U1") (pin "18") (pinfunction "~{RESET}_18") (pintype "bidirectional"))
      (node (ref "U1") (pin "9") (pinfunction "VDD_9") (pintype "power_in"))
      (node (ref "U2") (pin "18") (pinfunction "~{RESET}_18") (pintype "bidirectional"))
      (node (ref "U2") (pin "9") (pinfunction "VDD_9") (pintype "power_in"))
      (node (ref "U3") (pin "18") (pinfunction "~{RESET}_18") (pintype "bidirectional"))
      (node (ref "U3") (pin "9") (pinfunction "VDD_9") (pintype "power_in"))
      (node (ref "U4") (pin "18") (pinfunction "~{RESET}_18") (pintype "bidirectional"))
      (node (ref "U4") (pin "9") (pinfunction "VDD_9") (pintype "power_in"))
    )
    (net (code "89") (name "unconnected-(U1-NC-Pad11)") (class "Default")
      (node (ref "U1") (pin "11") (pinfunction "NC_11") (pintype "no_connect"))
    )
    (net (code "90") (name "unconnected-(U1-NC-Pad14)") (class "Default")
      (node (ref "U1") (pin "14") (pinfunction "NC_14") (pintype "no_connect"))
    )
    (net (code "91") (name "unconnected-(U2-NC-Pad11)") (class "Default")
      (node (ref "U2") (pin "11") (pinfunction "NC_11") (pintype "no_connect"))
    )
    (net (code "92") (name "unconnected-(U2-NC-Pad14)") (class "Default")
      (node (ref "U2") (pin "14") (pinfunction "NC_14") (pintype "no_connect"))
    )
    (net (code "93") (name "unconnected-(U3-NC-Pad11)") (class "Default")
      (node (ref "U3") (pin "11") (pinfunction "NC_11") (pintype "no_connect"))
    )
    (net (code "94") (name "unconnected-(U3-NC-Pad14)") (class "Default")
      (node (ref "U3") (pin "14") (pinfunction "NC_14") (pintype "no_connect"))
    )
    (net (code "95") (name "unconnected-(U4-NC-Pad11)") (class "Default")
      (node (ref "U4") (pin "11") (pinfunction "NC_11") (pintype "no_connect"))
    )
    (net (code "96") (name "unconnected-(U4-NC-Pad14)") (class "Default")
      (node (ref "U4") (pin "14") (pinfunction "NC_14") (pintype "no_connect"))
    )
  )
)
